# OZ440-SE100-CAR003_sheet6.net
KiCad netlist of a schematic drawn in Altium Designer
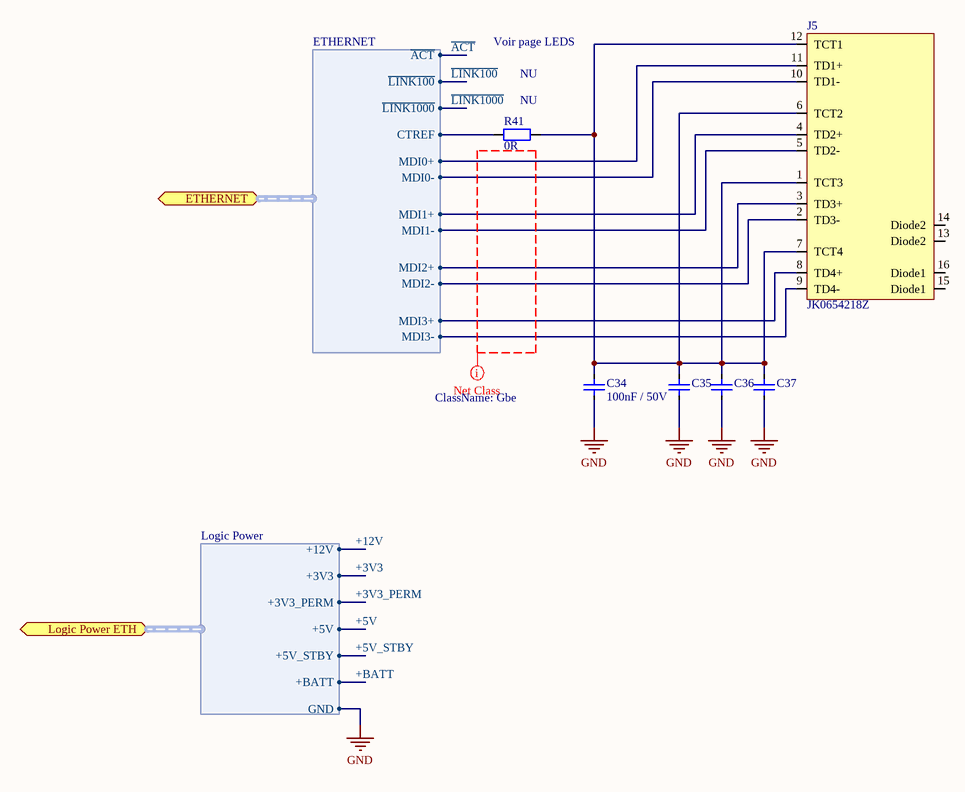
[diagram p0: OZ440-SE100-CAR003_sheet6.SchDoc]

(export (version "E")
  (design (tool "Eeschema 10.0.6"))
  (components
    (comp (ref "C34")
      (value "CAP-SMD")
      (footprint "C0805-STD")
      (description "0805 100nF / 50V  X7R ceramic capacitor")
      (fields
        (field (name "DISPLAYED REFERENCE") "100nF / 50V")
        (field (name "TOLERANCE") "+/- 10%")
        (field (name "MANUFACTURER") "vishay")
      )
      (libsource (lib "lib_NAIO") (part "CAP-SMD"))
    )
    (comp (ref "C35")
      (value "CAP-SMD")
      (footprint "C0805-STD")
      (description "0805 100nF / 50V  X7R ceramic capacitor")
      (fields (field (name "TOLERANCE") "+/- 10%") (field (name "MANUFACTURER") "vishay"))
      (libsource (lib "lib_NAIO") (part "CAP-SMD"))
    )
    (comp (ref "C36")
      (value "CAP-SMD")
      (footprint "C0805-STD")
      (description "0805 100nF / 50V  X7R ceramic capacitor")
      (fields (field (name "TOLERANCE") "+/- 10%") (field (name "MANUFACTURER") "vishay"))
      (libsource (lib "lib_NAIO") (part "CAP-SMD"))
    )
    (comp (ref "C37")
      (value "CAP-SMD")
      (footprint "C0805-STD")
      (description "0805 100nF / 50V  X7R ceramic capacitor")
      (fields (field (name "TOLERANCE") "+/- 10%") (field (name "MANUFACTURER") "vishay"))
      (libsource (lib "lib_NAIO") (part "CAP-SMD"))
    )
    (comp (ref "J5")
      (value "CONN_GIG_TF-SPE-PULSE_JK0654218Z")
      (footprint "TR-SPE-PULSE_JK0654X1XX")
      (description "Gigabit ethernet xformer with connector")
      (fields (field (name "DISPLAYED REFERENCE") "JK0654218Z") (field (name "MANUFACTURER") "PULSE"))
      (libsource (lib "lib_NAIO") (part "CONN_GIG_TF-SPE-PULSE_JK0654218Z"))
    )
    (comp (ref "R41")
      (value "RES-SMD")
      (footprint "R0805-STD")
      (description "0 Ohm 0805 SMD resistor")
      (fields
        (field (name "DISPLAYED REFERENCE") "0R")
        (field (name "TOLERANCE") "1%")
        (field (name "MANUFACTURER") "Vishay")
      )
      (libsource (lib "lib_NAIO") (part "RES-SMD"))
    )
  )
  (nets
    (net (code "11") (name "/CTREF") (class "Default")
      (node (ref "R41") (pin "1") (pinfunction "1_1") (pintype "passive"))
    )
    (net (code "14") (name "/MDI0+") (class "Default")
      (node (ref "J5") (pin "11") (pinfunction "TD1+_11") (pintype "passive"))
    )
    (net (code "15") (name "/MDI0-") (class "Default")
      (node (ref "J5") (pin "10") (pinfunction "TD1-_10") (pintype "passive"))
    )
    (net (code "16") (name "/MDI1+") (class "Default")
      (node (ref "J5") (pin "4") (pinfunction "TD2+_4") (pintype "passive"))
    )
    (net (code "17") (name "/MDI1-") (class "Default")
      (node (ref "J5") (pin "5") (pinfunction "TD2-_5") (pintype "passive"))
    )
    (net (code "18") (name "/MDI2+") (class "Default")
      (node (ref "J5") (pin "3") (pinfunction "TD3+_3") (pintype "passive"))
    )
    (net (code "19") (name "/MDI2-") (class "Default")
      (node (ref "J5") (pin "2") (pinfunction "TD3-_2") (pintype "passive"))
    )
    (net (code "20") (name "/MDI3+") (class "Default")
      (node (ref "J5") (pin "8") (pinfunction "TD4+_8") (pintype "passive"))
    )
    (net (code "21") (name "/MDI3-") (class "Default")
      (node (ref "J5") (pin "9") (pinfunction "TD4-_9") (pintype "passive"))
    )
    (net (code "24") (name "GND") (class "Default")
      (node (ref "C34") (pin "1") (pinfunction "1_1") (pintype "passive"))
      (node (ref "C35") (pin "1") (pinfunction "1_1") (pintype "passive"))
      (node (ref "C36") (pin "1") (pinfunction "1_1") (pintype "passive"))
      (node (ref "C37") (pin "1") (pinfunction "1_1") (pintype "passive"))
    )
    (net (code "25") (name "Net-(J5-TCT1)") (class "Default")
      (node (ref "C34") (pin "2") (pinfunction "2_2") (pintype "passive"))
      (node (ref "C35") (pin "2") (pinfunction "2_2") (pintype "passive"))
      (node (ref "C36") (pin "2") (pinfunction "2_2") (pintype "passive"))
      (node (ref "C37") (pin "2") (pinfunction "2_2") (pintype "passive"))
      (node (ref "J5") (pin "1") (pinfunction "TCT3_1") (pintype "passive"))
      (node (ref "J5") (pin "12") (pinfunction "TCT1_12") (pintype "passive"))
      (node (ref "J5") (pin "6") (pinfunction "TCT2_6") (pintype "passive"))
      (node (ref "J5") (pin "7") (pinfunction "TCT4_7") (pintype "passive"))
      (node (ref "R41") (pin "2") (pinfunction "2_2") (pintype "passive"))
    )
    (net (code "26") (name "unconnected-(J5-Diode1-Pad15)") (class "Default")
      (node (ref "J5") (pin "15") (pinfunction "Diode1_15") (pintype "passive"))
    )
    (net (code "27") (name "unconnected-(J5-Diode1-Pad16)") (class "Default")
      (node (ref "J5") (pin "16") (pinfunction "Diode1_16") (pintype "passive"))
    )
    (net (code "28") (name "unconnected-(J5-Diode2-Pad13)") (class "Default")
      (node (ref "J5") (pin "13") (pinfunction "Diode2_13") (pintype "passive"))
    )
    (net (code "29") (name "unconnected-(J5-Diode2-Pad14)") (class "Default")
      (node (ref "J5") (pin "14") (pinfunction "Diode2_14") (pintype "passive"))
    )
  )
)
